# Board.net
KiCad netlist of a schematic drawn in Altium Designer
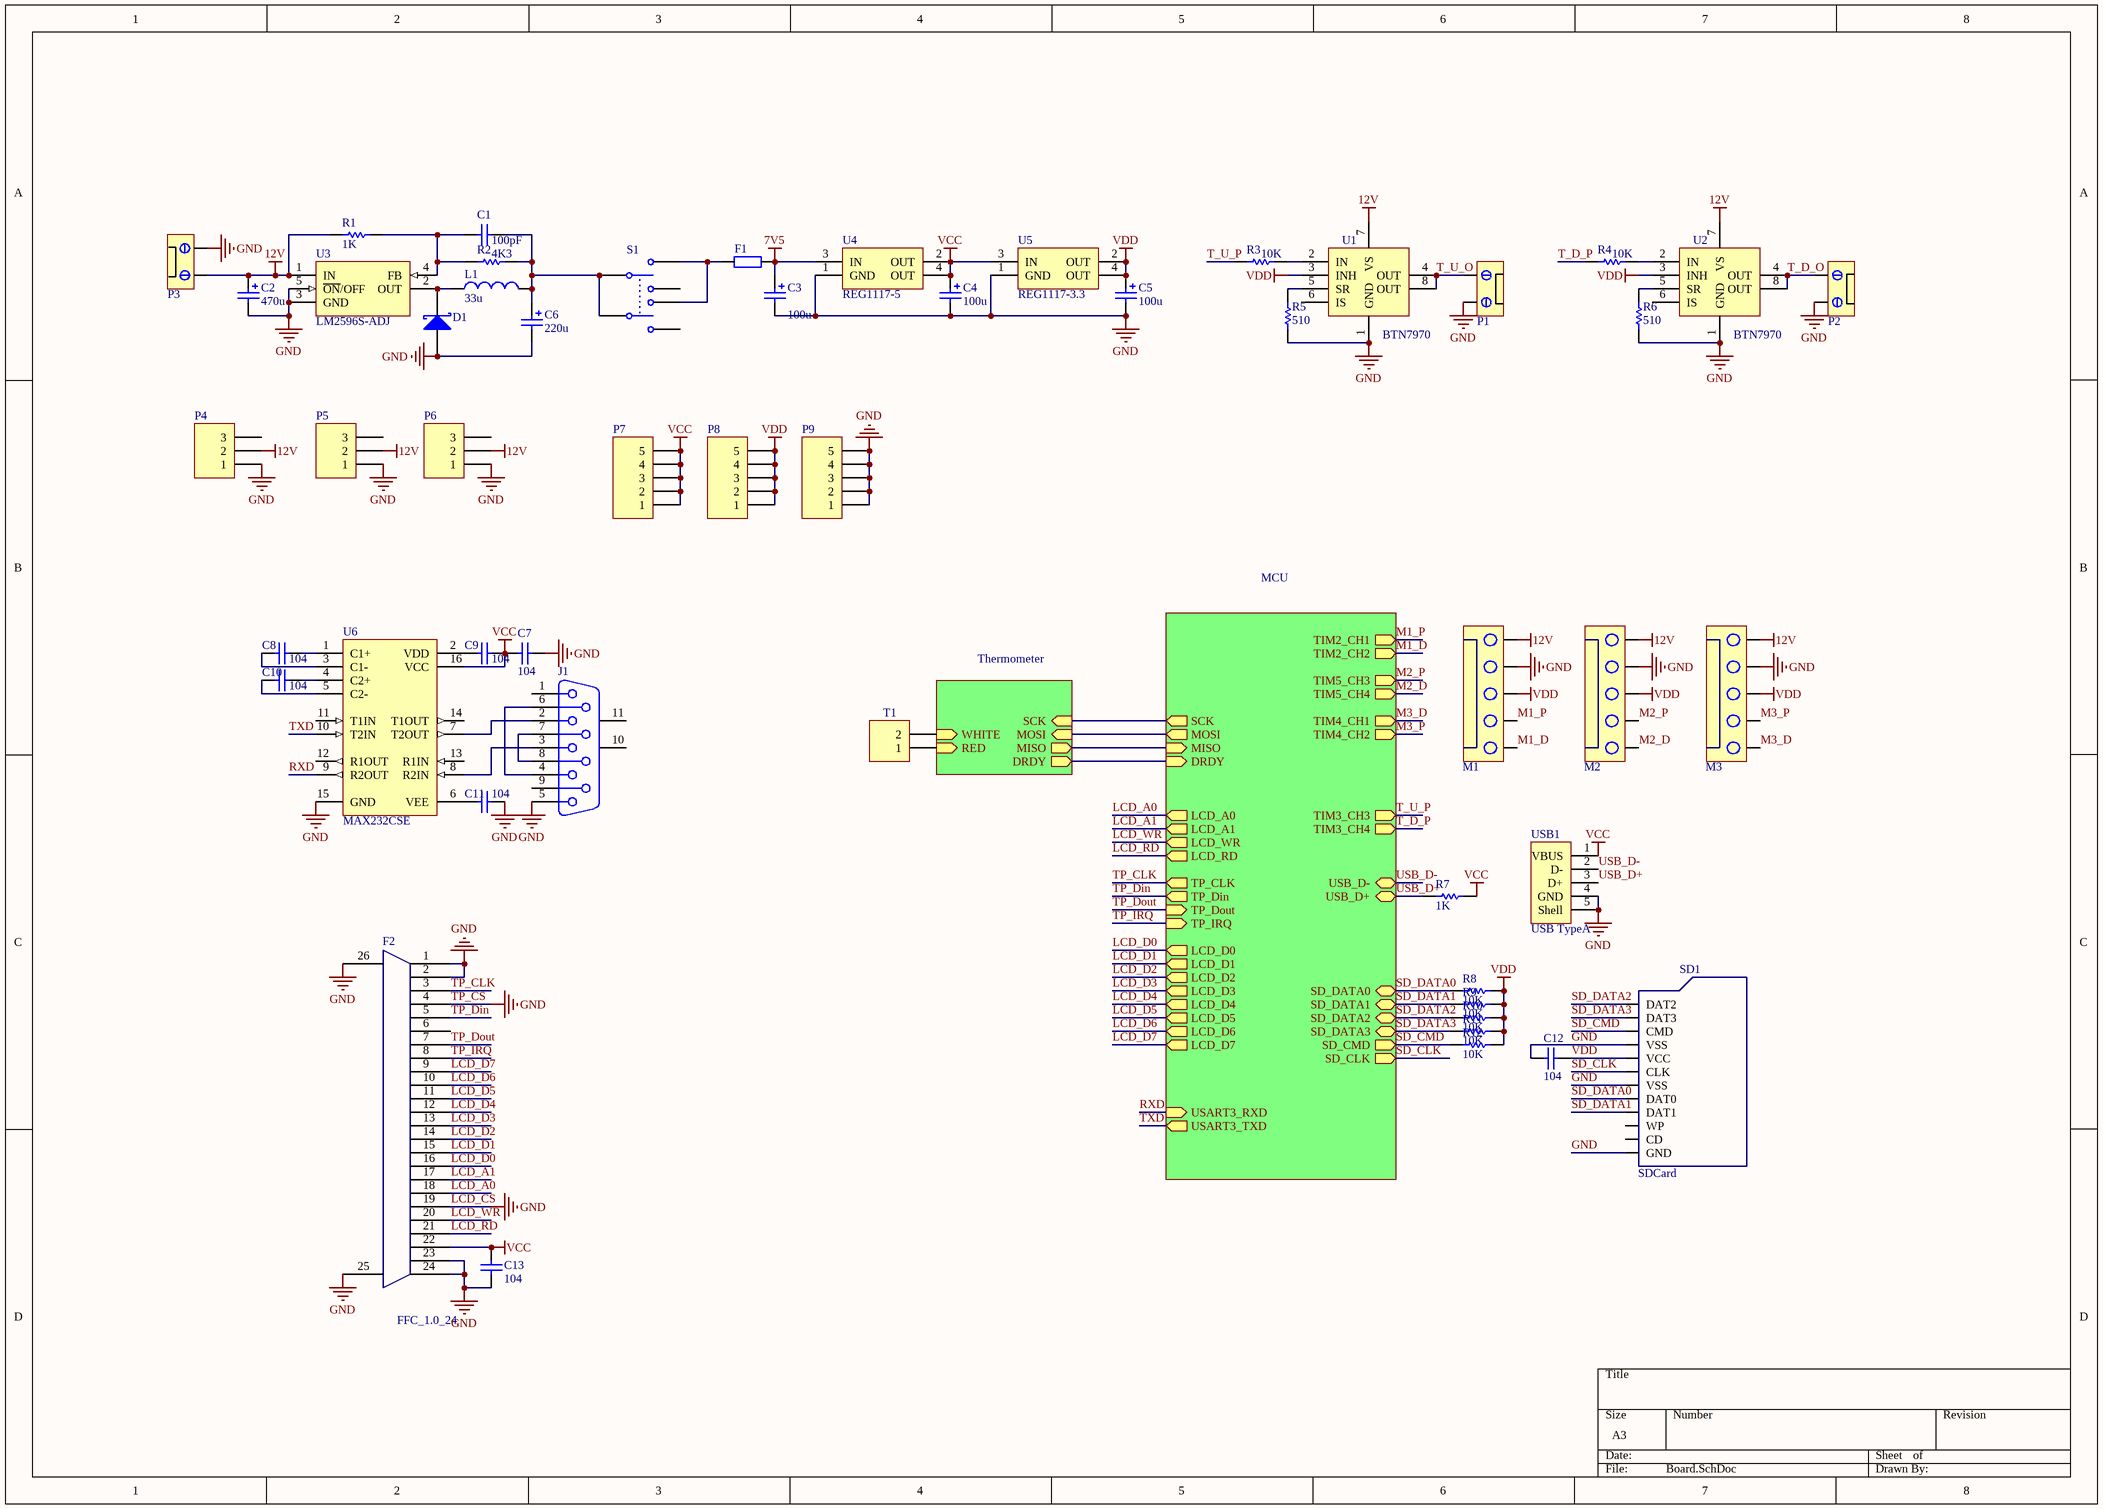
[diagram p0: Board.SchDoc]

(export (version "E")
  (design (tool "Eeschema 10.0.6"))
  (components
    (comp (ref "C1")
      (value "100pF")
      (footprint "CR2012-0805")
      (description "Capacitor")
      (fields (field (name "Comment") "Cap") (field (name "PUBLISHER") "Altium Limited"))
      (libsource (lib "ComDev") (part "Cap"))
    )
    (comp (ref "C2")
      (value "470u")
      (footprint "CAP POL Surface MOUNT-10")
      (description "Polarized Capacitor (Surface Mount)")
      (fields (field (name "Comment") "Cap Pol3") (field (name "PUBLISHER") "Altium Limited"))
      (libsource (lib "ComDev") (part "Cap Pol3"))
    )
    (comp (ref "C3")
      (value "100u")
      (footprint "CAP POL Surface Mount-6.3")
      (description "Polarized Capacitor (Surface Mount)")
      (fields (field (name "Comment") "Cap Pol3") (field (name "PUBLISHER") "Altium Limited"))
      (libsource (lib "ComDev") (part "Cap Pol3"))
    )
    (comp (ref "C4")
      (value "100u")
      (footprint "CAP POL Surface Mount-6.3")
      (description "Polarized Capacitor (Surface Mount)")
      (fields (field (name "Comment") "Cap Pol3") (field (name "PUBLISHER") "Altium Limited"))
      (libsource (lib "ComDev") (part "Cap Pol3"))
    )
    (comp (ref "C5")
      (value "100u")
      (footprint "CAP POL Surface Mount-6.3")
      (description "Polarized Capacitor (Surface Mount)")
      (fields (field (name "Comment") "Cap Pol3") (field (name "PUBLISHER") "Altium Limited"))
      (libsource (lib "ComDev") (part "Cap Pol3"))
    )
    (comp (ref "C6")
      (value "220u")
      (footprint "CAP POL Surface Mount-6.3")
      (description "Polarized Capacitor (Surface Mount)")
      (fields (field (name "Comment") "Cap Pol3") (field (name "PUBLISHER") "Altium Limited"))
      (libsource (lib "ComDev") (part "Cap Pol3"))
    )
    (comp (ref "C7")
      (value "104")
      (footprint "CR2012-0805")
      (description "Capacitor")
      (fields (field (name "Comment") "Cap") (field (name "PUBLISHER") "Altium Limited"))
      (libsource (lib "ComDev") (part "Cap"))
    )
    (comp (ref "C8")
      (value "104")
      (footprint "CR2012-0805")
      (description "Capacitor")
      (fields (field (name "Comment") "Cap") (field (name "PUBLISHER") "Altium Limited"))
      (libsource (lib "ComDev") (part "Cap"))
    )
    (comp (ref "C9")
      (value "104")
      (footprint "CR2012-0805")
      (description "Capacitor")
      (fields (field (name "Comment") "Cap") (field (name "PUBLISHER") "Altium Limited"))
      (libsource (lib "ComDev") (part "Cap"))
    )
    (comp (ref "C10")
      (value "104")
      (footprint "CR2012-0805")
      (description "Capacitor")
      (fields (field (name "Comment") "Cap") (field (name "PUBLISHER") "Altium Limited"))
      (libsource (lib "ComDev") (part "Cap"))
    )
    (comp (ref "C11")
      (value "104")
      (footprint "CR2012-0805")
      (description "Capacitor")
      (fields (field (name "Comment") "Cap") (field (name "PUBLISHER") "Altium Limited"))
      (libsource (lib "ComDev") (part "Cap"))
    )
    (comp (ref "C12")
      (value "104")
      (footprint "CR2012-0805")
      (description "Capacitor")
      (fields (field (name "Comment") "Cap") (field (name "PUBLISHER") "Altium Limited"))
      (libsource (lib "ComDev") (part "Cap"))
    )
    (comp (ref "C13")
      (value "104")
      (footprint "CR2012-0805")
      (description "Capacitor")
      (fields (field (name "Comment") "Cap") (field (name "PUBLISHER") "Altium Limited"))
      (libsource (lib "ComDev") (part "Cap"))
    )
    (comp (ref "D1")
      (value "D Schottky")
      (footprint "DSO-C2/X2.3")
      (description "Schottky Diode")
      (fields (field (name "PUBLISHER") "Altium Limited"))
      (libsource (lib "Miscellaneous Devices") (part "D Schottky"))
    )
    (comp (ref "F1") (value "FB") (footprint "CR2012-0805") (libsource (lib "ComDev") (part "FB")))
    (comp (ref "F2")
      (value "FFC_1.0_24")
      (footprint "FFC/SM1.0-2H24")
      (libsource (lib "ComDev") (part "FFC/SM1.0-2H24"))
    )
    (comp (ref "J1")
      (value "D Connector 9")
      (footprint "DSUB1.385-2H9")
      (description "Receptacle Assembly, 9 Position, Right Angle")
      (fields (field (name "PUBLISHER") "Altium Limited"))
      (libsource (lib "Miscellaneous Connectors") (part "D Connector 9"))
    )
    (comp (ref "L1")
      (value "33u")
      (footprint "inductor")
      (description "Inductor")
      (fields (field (name "PUBLISHER") "Altium Limited"))
      (libsource (lib "ComDev") (part "Inductor"))
    )
    (comp (ref "M1") (value "ConnP_5") (footprint "Conn_5-5.08") (libsource (lib "ComDev") (part "ConnP_5")))
    (comp (ref "M2") (value "ConnP_5") (footprint "Conn_5-5.08") (libsource (lib "ComDev") (part "ConnP_5")))
    (comp (ref "M3") (value "ConnP_5") (footprint "Conn_5-5.08") (libsource (lib "ComDev") (part "ConnP_5")))
    (comp (ref "P1") (value "ConnP_2") (footprint "Conn_2-5.08") (libsource (lib "ComDev") (part "ConnP_2")))
    (comp (ref "P2") (value "ConnP_2") (footprint "Conn_2-5.08") (libsource (lib "ComDev") (part "ConnP_2")))
    (comp (ref "P3") (value "ConnP_2") (footprint "Conn_2-5.08") (libsource (lib "") (part "ConnP_2_1")))
    (comp (ref "P4")
      (value "Header 3")
      (footprint "HDR1X3")
      (description "Header, 3-Pin")
      (fields (field (name "PUBLISHER") "Altium Limited"))
      (libsource (lib "Miscellaneous Connectors") (part "Header 3"))
    )
    (comp (ref "P5")
      (value "Header 3")
      (footprint "HDR1X3")
      (description "Header, 3-Pin")
      (fields (field (name "PUBLISHER") "Altium Limited"))
      (libsource (lib "Miscellaneous Connectors") (part "Header 3"))
    )
    (comp (ref "P6")
      (value "Header 3")
      (footprint "HDR1X3")
      (description "Header, 3-Pin")
      (fields (field (name "PUBLISHER") "Altium Limited"))
      (libsource (lib "Miscellaneous Connectors") (part "Header 3"))
    )
    (comp (ref "P7")
      (value "Header 5")
      (footprint "HDR1X5")
      (description "Header, 5-Pin")
      (fields (field (name "PUBLISHER") "Altium Limited"))
      (libsource (lib "Miscellaneous Connectors") (part "Header 5"))
    )
    (comp (ref "P8")
      (value "Header 5")
      (footprint "HDR1X5")
      (description "Header, 5-Pin")
      (fields (field (name "PUBLISHER") "Altium Limited"))
      (libsource (lib "Miscellaneous Connectors") (part "Header 5"))
    )
    (comp (ref "P9")
      (value "Header 5")
      (footprint "HDR1X5")
      (description "Header, 5-Pin")
      (fields (field (name "PUBLISHER") "Altium Limited"))
      (libsource (lib "Miscellaneous Connectors") (part "Header 5"))
    )
    (comp (ref "R1")
      (value "1K")
      (footprint "CR2012-0805")
      (description "Resistor")
      (fields (field (name "Comment") "Res") (field (name "PUBLISHER") "Altium Limited"))
      (libsource (lib "ComDev") (part "Res"))
    )
    (comp (ref "R2")
      (value "4K3")
      (footprint "CR2012-0805")
      (description "Resistor")
      (fields (field (name "Comment") "Res") (field (name "PUBLISHER") "Altium Limited"))
      (libsource (lib "ComDev") (part "Res"))
    )
    (comp (ref "R3")
      (value "10K")
      (footprint "CR2012-0805")
      (description "Resistor")
      (fields (field (name "Comment") "Res") (field (name "PUBLISHER") "Altium Limited"))
      (libsource (lib "ComDev") (part "Res"))
    )
    (comp (ref "R4")
      (value "10K")
      (footprint "CR2012-0805")
      (description "Resistor")
      (fields (field (name "Comment") "Res") (field (name "PUBLISHER") "Altium Limited"))
      (libsource (lib "ComDev") (part "Res"))
    )
    (comp (ref "R5")
      (value "510")
      (footprint "CR2012-0805")
      (description "Resistor")
      (fields (field (name "Comment") "Res") (field (name "PUBLISHER") "Altium Limited"))
      (libsource (lib "ComDev") (part "Res"))
    )
    (comp (ref "R6")
      (value "510")
      (footprint "CR2012-0805")
      (description "Resistor")
      (fields (field (name "Comment") "Res") (field (name "PUBLISHER") "Altium Limited"))
      (libsource (lib "ComDev") (part "Res"))
    )
    (comp (ref "R7")
      (value "1K")
      (footprint "CR2012-0805")
      (description "Resistor")
      (fields (field (name "Comment") "Res") (field (name "PUBLISHER") "Altium Limited"))
      (libsource (lib "ComDev") (part "Res"))
    )
    (comp (ref "R8")
      (value "10K")
      (footprint "CR2012-0805")
      (description "Resistor")
      (fields (field (name "Comment") "Res") (field (name "PUBLISHER") "Altium Limited"))
      (libsource (lib "ComDev") (part "Res"))
    )
    (comp (ref "R9")
      (value "10K")
      (footprint "CR2012-0805")
      (description "Resistor")
      (fields (field (name "Comment") "Res") (field (name "PUBLISHER") "Altium Limited"))
      (libsource (lib "ComDev") (part "Res"))
    )
    (comp (ref "R10")
      (value "10K")
      (footprint "CR2012-0805")
      (description "Resistor")
      (fields (field (name "Comment") "Res") (field (name "PUBLISHER") "Altium Limited"))
      (libsource (lib "ComDev") (part "Res"))
    )
    (comp (ref "R11")
      (value "10K")
      (footprint "CR2012-0805")
      (description "Resistor")
      (fields (field (name "Comment") "Res") (field (name "PUBLISHER") "Altium Limited"))
      (libsource (lib "ComDev") (part "Res"))
    )
    (comp (ref "R12")
      (value "10K")
      (footprint "CR2012-0805")
      (description "Resistor")
      (fields (field (name "Comment") "Res") (field (name "PUBLISHER") "Altium Limited"))
      (libsource (lib "ComDev") (part "Res"))
    )
    (comp (ref "S1")
      (value "SW-DPDT")
      (footprint "DPDT-6")
      (description "Double-Pole, Double-Throw Switch")
      (fields (field (name "PUBLISHER") "Altium Limited"))
      (libsource (lib "ComDev") (part "SW-DPDT"))
    )
    (comp (ref "SD1") (value "SDCard") (footprint "SDCARD") (libsource (lib "ComDev") (part "SDCard")))
    (comp (ref "T1")
      (value "Header 2")
      (footprint "HDR1X2")
      (description "Header, 2-Pin")
      (fields (field (name "PUBLISHER") "Altium Limited"))
      (libsource (lib "Miscellaneous Connectors") (part "Header 2"))
    )
    (comp (ref "U1") (value "BTN7970") (footprint "TS7B") (libsource (lib "ComDev") (part "BTN7970")))
    (comp (ref "U2") (value "BTN7970") (footprint "TS7B") (libsource (lib "ComDev") (part "BTN7970")))
    (comp (ref "U3")
      (value "LM2596S-ADJ")
      (footprint "TS5B")
      (description "Simple Switcher Power Converter 150 kHz 3A Step Down Voltage Regulator")
      (fields (field (name "PUBLISHER") "Altium Limited"))
      (libsource (lib "ComDev") (part "LM2596S-ADJ"))
    )
    (comp (ref "U4")
      (value "REG1117-5")
      (footprint "ZZ311")
      (description "800mA and 1A Low Dropout Positive Regulator 2.85V, 3.3V, 5V, and Adjustable")
      (fields (field (name "PUBLISHER") "Altium Limited"))
      (libsource (lib "BB Power Mgt Voltage Regulator") (part "REG1117-5"))
    )
    (comp (ref "U5")
      (value "REG1117-3.3")
      (footprint "ZZ311")
      (description "800mA and 1A Low Dropout Positive Regulator 2.85V, 3.3V, 5V, and Adjustable")
      (fields (field (name "PUBLISHER") "Altium Limited"))
      (libsource (lib "BB Power Mgt Voltage Regulator") (part "REG1117-3.3"))
    )
    (comp (ref "U6")
      (value "MAX232CSE")
      (footprint "NSO16")
      (description "+5V Powered, Multi-Channel RS-232 Driver/Receiver")
      (fields (field (name "PUBLISHER") "Altium Limited"))
      (libsource (lib "Maxim Communication Transceiver") (part "MAX232CSE"))
    )
    (comp (ref "USB1") (value "USB TypeA") (footprint "USB_A") (libsource (lib "ComDev") (part "USB_A")))
  )
  (nets
    (net (code "2") (name "/LCD_A0") (class "Default")
      (node (ref "F2") (pin "18") (pinfunction "17_18") (pintype "passive"))
    )
    (net (code "3") (name "/LCD_A1") (class "Default")
      (node (ref "F2") (pin "17") (pinfunction "16_17") (pintype "passive"))
    )
    (net (code "4") (name "/LCD_D0") (class "Default")
      (node (ref "F2") (pin "16") (pinfunction "15_16") (pintype "passive"))
    )
    (net (code "5") (name "/LCD_D1") (class "Default")
      (node (ref "F2") (pin "15") (pinfunction "14_15") (pintype "passive"))
    )
    (net (code "6") (name "/LCD_D2") (class "Default")
      (node (ref "F2") (pin "14") (pinfunction "13_14") (pintype "passive"))
    )
    (net (code "7") (name "/LCD_D3") (class "Default")
      (node (ref "F2") (pin "13") (pinfunction "12_13") (pintype "passive"))
    )
    (net (code "8") (name "/LCD_D4") (class "Default")
      (node (ref "F2") (pin "12") (pinfunction "11_12") (pintype "passive"))
    )
    (net (code "9") (name "/LCD_D5") (class "Default")
      (node (ref "F2") (pin "11") (pinfunction "10_11") (pintype "passive"))
    )
    (net (code "10") (name "/LCD_D6") (class "Default")
      (node (ref "F2") (pin "10") (pinfunction "9_10") (pintype "passive"))
    )
    (net (code "11") (name "/LCD_D7") (class "Default")
      (node (ref "F2") (pin "9") (pinfunction "8_9") (pintype "passive"))
    )
    (net (code "12") (name "/LCD_RD") (class "Default")
      (node (ref "F2") (pin "21") (pinfunction "20_21") (pintype "passive"))
    )
    (net (code "13") (name "/LCD_WR") (class "Default")
      (node (ref "F2") (pin "20") (pinfunction "19_20") (pintype "passive"))
    )
    (net (code "14") (name "/M1_D") (class "Default")
      (node (ref "M1") (pin "1") (pinfunction "0_1") (pintype "passive"))
    )
    (net (code "15") (name "/M1_P") (class "Default")
      (node (ref "M1") (pin "2") (pinfunction "1_2") (pintype "passive"))
    )
    (net (code "16") (name "/M2_D") (class "Default")
      (node (ref "M2") (pin "1") (pinfunction "0_1") (pintype "passive"))
    )
    (net (code "17") (name "/M2_P") (class "Default")
      (node (ref "M2") (pin "2") (pinfunction "1_2") (pintype "passive"))
    )
    (net (code "18") (name "/M3_D") (class "Default")
      (node (ref "M3") (pin "1") (pinfunction "0_1") (pintype "passive"))
    )
    (net (code "19") (name "/M3_P") (class "Default")
      (node (ref "M3") (pin "2") (pinfunction "1_2") (pintype "passive"))
    )
    (net (code "22") (name "/RED") (class "Default")
      (node (ref "T1") (pin "1") (pinfunction "1_1") (pintype "passive"))
    )
    (net (code "23") (name "/RXD") (class "Default")
      (node (ref "U6") (pin "9") (pinfunction "R2OUT_9") (pintype "output"))
    )
    (net (code "25") (name "/SD_CLK") (class "Default")
      (node (ref "SD1") (pin "5") (pinfunction "CLK_5") (pintype "passive"))
    )
    (net (code "26") (name "/SD_CMD") (class "Default")
      (node (ref "R12") (pin "1") (pinfunction "1_1") (pintype "passive"))
      (node (ref "SD1") (pin "2") (pinfunction "CMD_2") (pintype "passive"))
    )
    (net (code "27") (name "/SD_DATA0") (class "Default")
      (node (ref "R8") (pin "1") (pinfunction "1_1") (pintype "passive"))
      (node (ref "SD1") (pin "7") (pinfunction "DAT0_7") (pintype "passive"))
    )
    (net (code "28") (name "/SD_DATA1") (class "Default")
      (node (ref "R9") (pin "1") (pinfunction "1_1") (pintype "passive"))
      (node (ref "SD1") (pin "8") (pinfunction "DAT1_8") (pintype "passive"))
    )
    (net (code "29") (name "/SD_DATA2") (class "Default")
      (node (ref "R10") (pin "1") (pinfunction "1_1") (pintype "passive"))
      (node (ref "SD1") (pin "9") (pinfunction "DAT2_9") (pintype "passive"))
    )
    (net (code "30") (name "/SD_DATA3") (class "Default")
      (node (ref "R11") (pin "1") (pinfunction "1_1") (pintype "passive"))
      (node (ref "SD1") (pin "1") (pinfunction "DAT3_1") (pintype "passive"))
    )
    (net (code "31") (name "/TP_CLK") (class "Default")
      (node (ref "F2") (pin "3") (pinfunction "2_3") (pintype "passive"))
    )
    (net (code "32") (name "/TP_Din") (class "Default")
      (node (ref "F2") (pin "5") (pinfunction "4_5") (pintype "passive"))
    )
    (net (code "33") (name "/TP_Dout") (class "Default")
      (node (ref "F2") (pin "7") (pinfunction "6_7") (pintype "passive"))
    )
    (net (code "34") (name "/TP_IRQ") (class "Default")
      (node (ref "F2") (pin "8") (pinfunction "7_8") (pintype "passive"))
    )
    (net (code "35") (name "/TXD") (class "Default")
      (node (ref "U6") (pin "10") (pinfunction "T2IN_10") (pintype "input"))
    )
    (net (code "36") (name "/T_D_O") (class "Default")
      (node (ref "P2") (pin "1") (pintype "power_in"))
      (node (ref "U2") (pin "4") (pinfunction "OUT_4") (pintype "passive"))
      (node (ref "U2") (pin "8") (pinfunction "OUT_8") (pintype "passive"))
    )
    (net (code "37") (name "/T_D_P") (class "Default")
      (node (ref "R4") (pin "1") (pinfunction "1_1") (pintype "passive"))
    )
    (net (code "38") (name "/T_U_O") (class "Default")
      (node (ref "P1") (pin "1") (pintype "power_in"))
      (node (ref "U1") (pin "4") (pinfunction "OUT_4") (pintype "passive"))
      (node (ref "U1") (pin "8") (pinfunction "OUT_8") (pintype "passive"))
    )
    (net (code "39") (name "/T_U_P") (class "Default")
      (node (ref "R3") (pin "1") (pinfunction "1_1") (pintype "passive"))
    )
    (net (code "40") (name "/USB_D+") (class "Default")
      (node (ref "R7") (pin "2") (pinfunction "2_2") (pintype "passive"))
      (node (ref "USB1") (pin "3") (pinfunction "D+_3") (pintype "passive"))
    )
    (net (code "41") (name "/USB_D-") (class "Default")
      (node (ref "USB1") (pin "2") (pinfunction "D-_2") (pintype "passive"))
    )
    (net (code "42") (name "/WHITE") (class "Default")
      (node (ref "T1") (pin "2") (pinfunction "2_2") (pintype "passive"))
    )
    (net (code "43") (name "7V5") (class "Default")
      (node (ref "C3") (pin "1") (pinfunction "1_1") (pintype "passive"))
      (node (ref "F1") (pin "2") (pinfunction "2_2") (pintype "passive"))
      (node (ref "U4") (pin "3") (pinfunction "IN_3") (pintype "power_in"))
    )
    (net (code "44") (name "12V") (class "Default")
      (node (ref "C2") (pin "1") (pinfunction "1_1") (pintype "passive"))
      (node (ref "M1") (pin "5") (pinfunction "5_5") (pintype "passive"))
      (node (ref "M2") (pin "5") (pinfunction "5_5") (pintype "passive"))
      (node (ref "M3") (pin "5") (pinfunction "5_5") (pintype "passive"))
      (node (ref "P3") (pin "1") (pintype "power_in"))
      (node (ref "P4") (pin "2") (pinfunction "2_2") (pintype "passive"))
      (node (ref "P5") (pin "2") (pinfunction "2_2") (pintype "passive"))
      (node (ref "P6") (pin "2") (pinfunction "2_2") (pintype "passive"))
      (node (ref "R1") (pin "1") (pinfunction "1_1") (pintype "passive"))
      (node (ref "U1") (pin "7") (pinfunction "VS_7") (pintype "passive"))
      (node (ref "U2") (pin "7") (pinfunction "VS_7") (pintype "passive"))
      (node (ref "U3") (pin "1") (pinfunction "IN_1") (pintype "power_in"))
    )
    (net (code "45") (name "GND") (class "Default")
      (node (ref "C11") (pin "1") (pinfunction "1_1") (pintype "passive"))
      (node (ref "C12") (pin "1") (pinfunction "1_1") (pintype "passive"))
      (node (ref "C13") (pin "1") (pinfunction "1_1") (pintype "passive"))
      (node (ref "C2") (pin "2") (pinfunction "2_2") (pintype "passive"))
      (node (ref "C3") (pin "2") (pinfunction "2_2") (pintype "passive"))
      (node (ref "C4") (pin "2") (pinfunction "2_2") (pintype "passive"))
      (node (ref "C5") (pin "2") (pinfunction "2_2") (pintype "passive"))
      (node (ref "C6") (pin "2") (pinfunction "2_2") (pintype "passive"))
      (node (ref "C7") (pin "1") (pinfunction "1_1") (pintype "passive"))
      (node (ref "D1") (pin "1") (pinfunction "A_1") (pintype "passive"))
      (node (ref "F2") (pin "1") (pinfunction "0_1") (pintype "passive"))
      (node (ref "F2") (pin "19") (pinfunction "18_19") (pintype "passive"))
      (node (ref "F2") (pin "2") (pinfunction "1_2") (pintype "passive"))
      (node (ref "F2") (pin "23") (pinfunction "22_23") (pintype "passive"))
      (node (ref "F2") (pin "24") (pinfunction "23_24") (pintype "passive"))
      (node (ref "F2") (pin "25") (pinfunction "25_25") (pintype "passive"))
      (node (ref "F2") (pin "26") (pinfunction "26_26") (pintype "passive"))
      (node (ref "F2") (pin "4") (pinfunction "3_4") (pintype "passive"))
      (node (ref "J1") (pin "5") (pinfunction "5_5") (pintype "passive"))
      (node (ref "M1") (pin "4") (pinfunction "4_4") (pintype "passive"))
      (node (ref "M2") (pin "4") (pinfunction "4_4") (pintype "passive"))
      (node (ref "M3") (pin "4") (pinfunction "4_4") (pintype "passive"))
      (node (ref "P1") (pin "2") (pintype "power_in"))
      (node (ref "P2") (pin "2") (pintype "power_in"))
      (node (ref "P3") (pin "2") (pintype "power_in"))
      (node (ref "P4") (pin "1") (pinfunction "1_1") (pintype "passive"))
      (node (ref "P5") (pin "1") (pinfunction "1_1") (pintype "passive"))
      (node (ref "P6") (pin "1") (pinfunction "1_1") (pintype "passive"))
      (node (ref "P9") (pin "1") (pinfunction "1_1") (pintype "passive"))
      (node (ref "P9") (pin "2") (pinfunction "2_2") (pintype "passive"))
      (node (ref "P9") (pin "3") (pinfunction "3_3") (pintype "passive"))
      (node (ref "P9") (pin "4") (pinfunction "4_4") (pintype "passive"))
      (node (ref "P9") (pin "5") (pinfunction "5_5") (pintype "passive"))
      (node (ref "R5") (pin "1") (pinfunction "1_1") (pintype "passive"))
      (node (ref "R6") (pin "1") (pinfunction "1_1") (pintype "passive"))
      (node (ref "SD1") (pin "0") (pinfunction "GND_0") (pintype "passive"))
      (node (ref "SD1") (pin "3") (pinfunction "VSS_3") (pintype "passive"))
      (node (ref "SD1") (pin "6") (pinfunction "VSS_6") (pintype "passive"))
      (node (ref "U1") (pin "1") (pinfunction "GND_1") (pintype "passive"))
      (node (ref "U2") (pin "1") (pinfunction "GND_1") (pintype "passive"))
      (node (ref "U3") (pin "3") (pinfunction "GND_3") (pintype "power_in"))
      (node (ref "U3") (pin "5") (pinfunction "~{ON}/OFF_5") (pintype "input"))
      (node (ref "U4") (pin "1") (pinfunction "GND_1") (pintype "power_in"))
      (node (ref "U5") (pin "1") (pinfunction "GND_1") (pintype "power_in"))
      (node (ref "U6") (pin "15") (pinfunction "GND_15") (pintype "power_in"))
      (node (ref "USB1") (pin "4") (pinfunction "GND_4") (pintype "passive"))
      (node (ref "USB1") (pin "5") (pinfunction "Shell_5") (pintype "passive"))
    )
    (net (code "46") (name "Net-(C1-Pad2)") (class "Default")
      (node (ref "C1") (pin "2") (pinfunction "2_2") (pintype "passive"))
      (node (ref "C6") (pin "1") (pinfunction "1_1") (pintype "passive"))
      (node (ref "L1") (pin "2") (pinfunction "2_2") (pintype "passive"))
      (node (ref "R2") (pin "2") (pinfunction "2_2") (pintype "passive"))
      (node (ref "S1") (pin "2") (pinfunction "2_2") (pintype "passive"))
      (node (ref "S1") (pin "5") (pinfunction "5_5") (pintype "passive"))
    )
    (net (code "47") (name "Net-(D1-K)") (class "Default")
      (node (ref "D1") (pin "2") (pinfunction "K_2") (pintype "passive"))
      (node (ref "L1") (pin "1") (pinfunction "1_1") (pintype "passive"))
      (node (ref "U3") (pin "2") (pinfunction "OUT_2") (pintype "power_in"))
    )
    (net (code "48") (name "Net-(F1-Pad1)") (class "Default")
      (node (ref "F1") (pin "1") (pinfunction "1_1") (pintype "passive"))
      (node (ref "S1") (pin "1") (pinfunction "1_1") (pintype "passive"))
      (node (ref "S1") (pin "6") (pinfunction "6_6") (pintype "passive"))
    )
    (net (code "49") (name "Net-(J1-Pad4)") (class "Default")
      (node (ref "J1") (pin "4") (pinfunction "4_4") (pintype "passive"))
      (node (ref "J1") (pin "6") (pinfunction "6_6") (pintype "passive"))
    )
    (net (code "50") (name "Net-(J1-Pad7)") (class "Default")
      (node (ref "J1") (pin "7") (pinfunction "7_7") (pintype "passive"))
      (node (ref "J1") (pin "8") (pinfunction "8_8") (pintype "passive"))
    )
    (net (code "51") (name "Net-(U1-IN)") (class "Default")
      (node (ref "R3") (pin "2") (pinfunction "2_2") (pintype "passive"))
      (node (ref "U1") (pin "2") (pinfunction "IN_2") (pintype "passive"))
    )
    (net (code "52") (name "Net-(U1-SR)") (class "Default")
      (node (ref "R5") (pin "2") (pinfunction "2_2") (pintype "passive"))
      (node (ref "U1") (pin "5") (pinfunction "SR_5") (pintype "passive"))
    )
    (net (code "53") (name "Net-(U2-IN)") (class "Default")
      (node (ref "R4") (pin "2") (pinfunction "2_2") (pintype "passive"))
      (node (ref "U2") (pin "2") (pinfunction "IN_2") (pintype "passive"))
    )
    (net (code "54") (name "Net-(U2-SR)") (class "Default")
      (node (ref "R6") (pin "2") (pinfunction "2_2") (pintype "passive"))
      (node (ref "U2") (pin "5") (pinfunction "SR_5") (pintype "passive"))
    )
    (net (code "55") (name "Net-(U3-FB)") (class "Default")
      (node (ref "C1") (pin "1") (pinfunction "1_1") (pintype "passive"))
      (node (ref "R1") (pin "2") (pinfunction "2_2") (pintype "passive"))
      (node (ref "R2") (pin "1") (pinfunction "1_1") (pintype "passive"))
      (node (ref "U3") (pin "4") (pinfunction "FB_4") (pintype "input"))
    )
    (net (code "56") (name "Net-(U6-C1+)") (class "Default")
      (node (ref "C8") (pin "1") (pinfunction "1_1") (pintype "passive"))
      (node (ref "U6") (pin "1") (pinfunction "C1+_1") (pintype "passive"))
    )
    (net (code "57") (name "Net-(U6-C1-)") (class "Default")
      (node (ref "C8") (pin "2") (pinfunction "2_2") (pintype "passive"))
      (node (ref "U6") (pin "3") (pinfunction "C1-_3") (pintype "passive"))
    )
    (net (code "58") (name "Net-(U6-C2+)") (class "Default")
      (node (ref "C10") (pin "1") (pinfunction "1_1") (pintype "passive"))
      (node (ref "U6") (pin "4") (pinfunction "C2+_4") (pintype "passive"))
    )
    (net (code "59") (name "Net-(U6-C2-)") (class "Default")
      (node (ref "C10") (pin "2") (pinfunction "2_2") (pintype "passive"))
      (node (ref "U6") (pin "5") (pinfunction "C2-_5") (pintype "passive"))
    )
    (net (code "60") (name "Net-(U6-R2IN)") (class "Default")
      (node (ref "J1") (pin "3") (pinfunction "3_3") (pintype "passive"))
      (node (ref "U6") (pin "8") (pinfunction "R2IN_8") (pintype "input"))
    )
    (net (code "61") (name "Net-(U6-T2OUT)") (class "Default")
      (node (ref "J1") (pin "2") (pinfunction "2_2") (pintype "passive"))
      (node (ref "U6") (pin "7") (pinfunction "T2OUT_7") (pintype "output"))
    )
    (net (code "62") (name "Net-(U6-VDD)") (class "Default")
      (node (ref "C9") (pin "2") (pinfunction "2_2") (pintype "passive"))
      (node (ref "U6") (pin "2") (pinfunction "VDD_2") (pintype "power_in"))
    )
    (net (code "63") (name "Net-(U6-VEE)") (class "Default")
      (node (ref "C11") (pin "2") (pinfunction "2_2") (pintype "passive"))
      (node (ref "U6") (pin "6") (pinfunction "VEE_6") (pintype "power_in"))
    )
    (net (code "64") (name "VCC") (class "Default")
      (node (ref "C13") (pin "2") (pinfunction "2_2") (pintype "passive"))
      (node (ref "C4") (pin "1") (pinfunction "1_1") (pintype "passive"))
      (node (ref "C7") (pin "2") (pinfunction "2_2") (pintype "passive"))
      (node (ref "C9") (pin "1") (pinfunction "1_1") (pintype "passive"))
      (node (ref "F2") (pin "22") (pinfunction "21_22") (pintype "passive"))
      (node (ref "P7") (pin "1") (pinfunction "1_1") (pintype "passive"))
      (node (ref "P7") (pin "2") (pinfunction "2_2") (pintype "passive"))
      (node (ref "P7") (pin "3") (pinfunction "3_3") (pintype "passive"))
      (node (ref "P7") (pin "4") (pinfunction "4_4") (pintype "passive"))
      (node (ref "P7") (pin "5") (pinfunction "5_5") (pintype "passive"))
      (node (ref "R7") (pin "1") (pinfunction "1_1") (pintype "passive"))
      (node (ref "U4") (pin "2") (pinfunction "OUT_2") (pintype "power_in"))
      (node (ref "U4") (pin "4") (pinfunction "OUT_4") (pintype "power_in"))
      (node (ref "U5") (pin "3") (pinfunction "IN_3") (pintype "power_in"))
      (node (ref "U6") (pin "16") (pinfunction "VCC_16") (pintype "power_in"))
      (node (ref "USB1") (pin "1") (pinfunction "VBUS_1") (pintype "passive"))
    )
    (net (code "65") (name "VDD") (class "Default")
      (node (ref "C12") (pin "2") (pinfunction "2_2") (pintype "passive"))
      (node (ref "C5") (pin "1") (pinfunction "1_1") (pintype "passive"))
      (node (ref "M1") (pin "3") (pinfunction "2_3") (pintype "passive"))
      (node (ref "M2") (pin "3") (pinfunction "2_3") (pintype "passive"))
      (node (ref "M3") (pin "3") (pinfunction "2_3") (pintype "passive"))
      (node (ref "P8") (pin "1") (pinfunction "1_1") (pintype "passive"))
      (node (ref "P8") (pin "2") (pinfunction "2_2") (pintype "passive"))
      (node (ref "P8") (pin "3") (pinfunction "3_3") (pintype "passive"))
      (node (ref "P8") (pin "4") (pinfunction "4_4") (pintype "passive"))
      (node (ref "P8") (pin "5") (pinfunction "5_5") (pintype "passive"))
      (node (ref "R10") (pin "2") (pinfunction "2_2") (pintype "passive"))
      (node (ref "R11") (pin "2") (pinfunction "2_2") (pintype "passive"))
      (node (ref "R12") (pin "2") (pinfunction "2_2") (pintype "passive"))
      (node (ref "R8") (pin "2") (pinfunction "2_2") (pintype "passive"))
      (node (ref "R9") (pin "2") (pinfunction "2_2") (pintype "passive"))
      (node (ref "SD1") (pin "4") (pinfunction "VCC_4") (pintype "passive"))
      (node (ref "U1") (pin "3") (pinfunction "INH_3") (pintype "passive"))
      (node (ref "U2") (pin "3") (pinfunction "INH_3") (pintype "passive"))
      (node (ref "U5") (pin "2") (pinfunction "OUT_2") (pintype "power_in"))
      (node (ref "U5") (pin "4") (pinfunction "OUT_4") (pintype "power_in"))
    )
    (net (code "66") (name "unconnected-(F2-5-Pad6)") (class "Default")
      (node (ref "F2") (pin "6") (pinfunction "5_6") (pintype "passive"))
    )
    (net (code "67") (name "unconnected-(J1-MH1-Pad10)") (class "Default")
      (node (ref "J1") (pin "10") (pinfunction "MH1_10") (pintype "passive"))
    )
    (net (code "68") (name "unconnected-(J1-MH2-Pad11)") (class "Default")
      (node (ref "J1") (pin "11") (pinfunction "MH2_11") (pintype "passive"))
    )
    (net (code "69") (name "unconnected-(J1-Pad1)") (class "Default")
      (node (ref "J1") (pin "1") (pinfunction "1_1") (pintype "passive"))
    )
    (net (code "70") (name "unconnected-(J1-Pad9)") (class "Default")
      (node (ref "J1") (pin "9") (pinfunction "9_9") (pintype "passive"))
    )
    (net (code "71") (name "unconnected-(P4-Pad3)") (class "Default")
      (node (ref "P4") (pin "3") (pinfunction "3_3") (pintype "passive"))
    )
    (net (code "72") (name "unconnected-(P5-Pad3)") (class "Default")
      (node (ref "P5") (pin "3") (pinfunction "3_3") (pintype "passive"))
    )
    (net (code "73") (name "unconnected-(P6-Pad3)") (class "Default")
      (node (ref "P6") (pin "3") (pinfunction "3_3") (pintype "passive"))
    )
    (net (code "74") (name "unconnected-(S1-Pad3)") (class "Default")
      (node (ref "S1") (pin "3") (pinfunction "3_3") (pintype "passive"))
    )
    (net (code "75") (name "unconnected-(S1-Pad4)") (class "Default")
      (node (ref "S1") (pin "4") (pinfunction "4_4") (pintype "passive"))
    )
    (net (code "76") (name "unconnected-(SD1-CD-Pad11)") (class "Default")
      (node (ref "SD1") (pin "11") (pinfunction "CD_11") (pintype "passive"))
    )
    (net (code "77") (name "unconnected-(SD1-WP-Pad10)") (class "Default")
      (node (ref "SD1") (pin "10") (pinfunction "WP_10") (pintype "passive"))
    )
    (net (code "78") (name "unconnected-(U1-IS-Pad6)") (class "Default")
      (node (ref "U1") (pin "6") (pinfunction "IS_6") (pintype "passive"))
    )
    (net (code "79") (name "unconnected-(U2-IS-Pad6)") (class "Default")
      (node (ref "U2") (pin "6") (pinfunction "IS_6") (pintype "passive"))
    )
    (net (code "80") (name "unconnected-(U6-R1IN-Pad13)") (class "Default")
      (node (ref "U6") (pin "13") (pinfunction "R1IN_13") (pintype "input"))
    )
    (net (code "81") (name "unconnected-(U6-R1OUT-Pad12)") (class "Default")
      (node (ref "U6") (pin "12") (pinfunction "R1OUT_12") (pintype "output"))
    )
    (net (code "82") (name "unconnected-(U6-T1IN-Pad11)") (class "Default")
      (node (ref "U6") (pin "11") (pinfunction "T1IN_11") (pintype "input"))
    )
    (net (code "83") (name "unconnected-(U6-T1OUT-Pad14)") (class "Default")
      (node (ref "U6") (pin "14") (pinfunction "T1OUT_14") (pintype "output"))
    )
  )
)
